# dcf77_clock.net
KiCad netlist of a schematic drawn in EAGLE
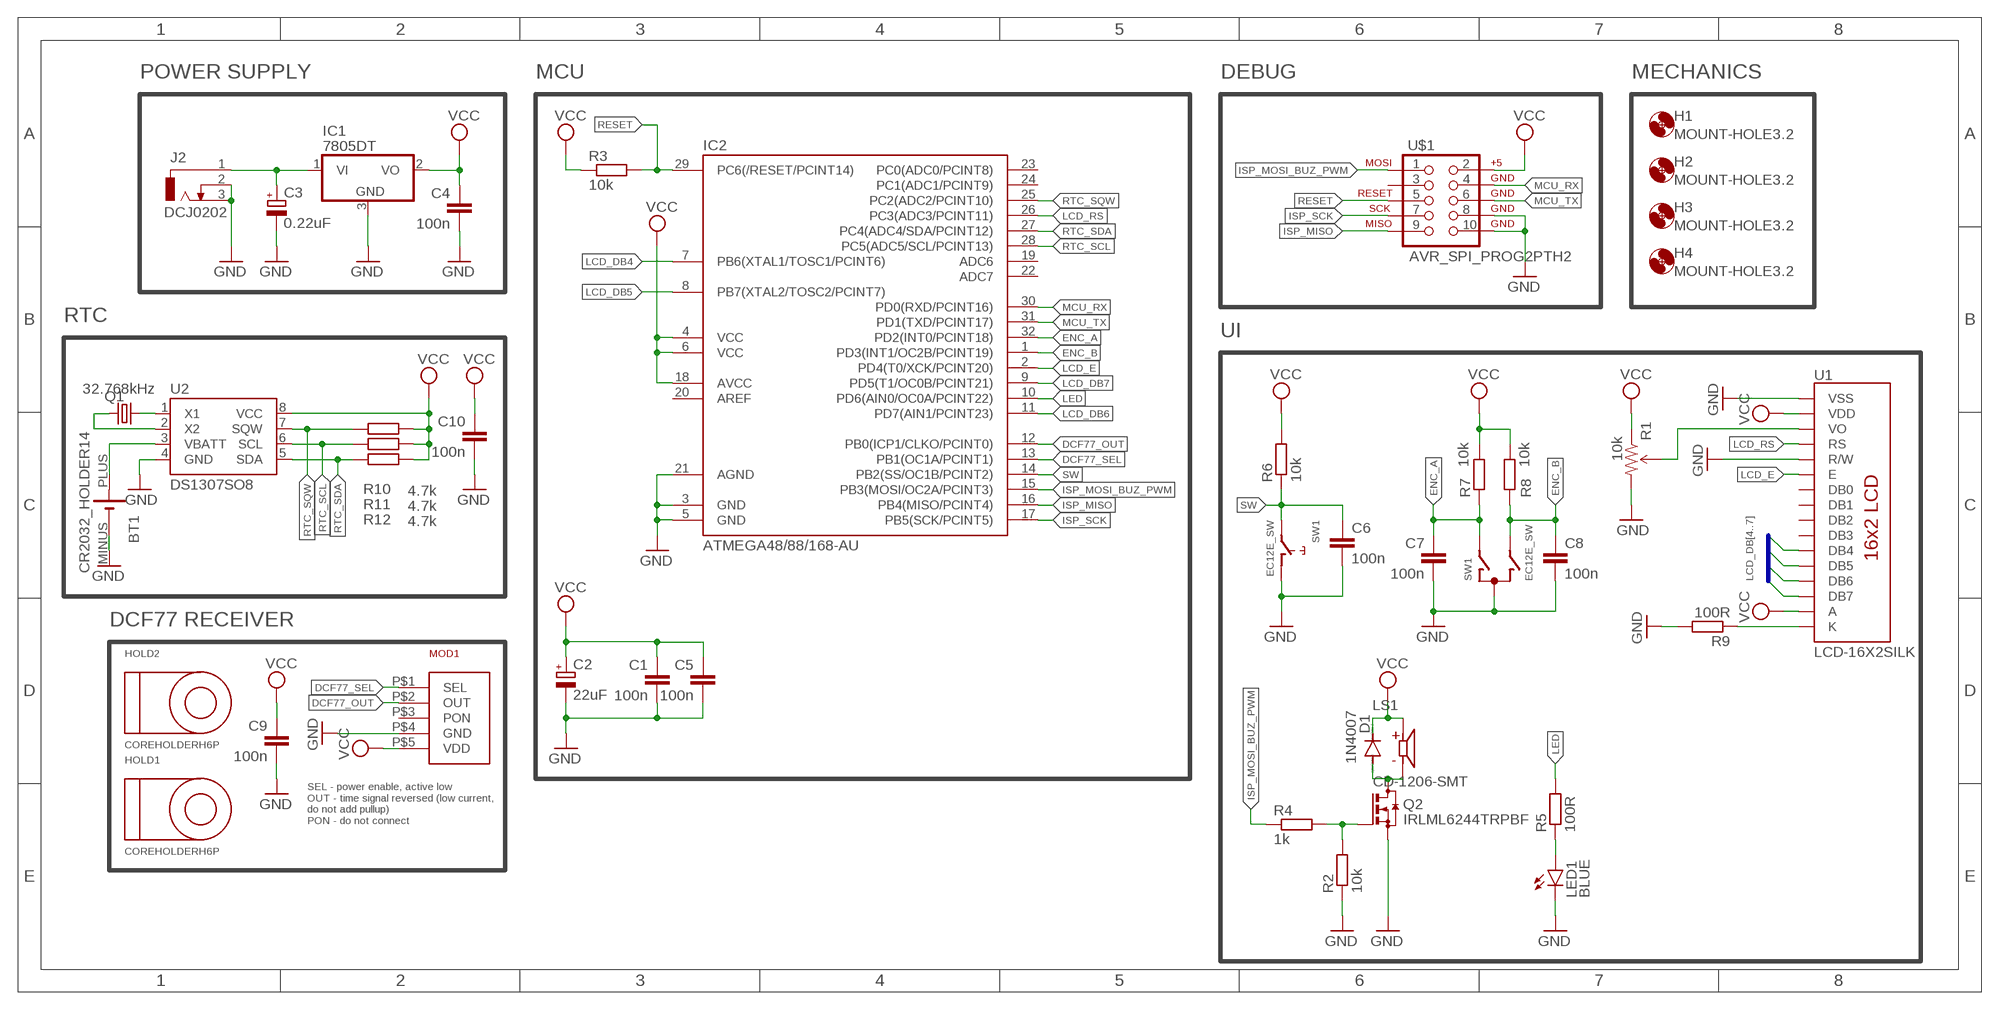
[diagram p0: schematic, sheet 1]

(export (version "E")
  (design (tool "Eeschema 10.0.6"))
  (components
    (comp (ref "BT1")
      (value "CR2032_HOLDER14")
      (footprint "eagle-import:CONNFLY-DS1092-14-B6P")
      (libsource (lib "eagle-import") (part "CR2032_HOLDER14"))
    )
    (comp (ref "C1")
      (value "100n")
      (footprint "eagle-import:C0805K")
      (libsource (lib "eagle-import") (part "C-EUC0805K"))
    )
    (comp (ref "C2")
      (value "22uF")
      (footprint "eagle-import:UD-4X5,8_NICHICON")
      (libsource (lib "eagle-import") (part "CPOL-EUUD-4X5,8"))
    )
    (comp (ref "C3")
      (value "0.22uF")
      (footprint "eagle-import:SMC_Z")
      (libsource (lib "eagle-import") (part "CPOL-EUSMCZ"))
    )
    (comp (ref "C4")
      (value "100n")
      (footprint "eagle-import:C0805K")
      (libsource (lib "eagle-import") (part "C-EUC0805K"))
    )
    (comp (ref "C5")
      (value "100n")
      (footprint "eagle-import:C0805K")
      (libsource (lib "eagle-import") (part "C-EUC0805K"))
    )
    (comp (ref "C6")
      (value "100n")
      (footprint "eagle-import:C0805K")
      (libsource (lib "eagle-import") (part "C-EUC0805K"))
    )
    (comp (ref "C7")
      (value "100n")
      (footprint "eagle-import:C0805K")
      (libsource (lib "eagle-import") (part "C-EUC0805K"))
    )
    (comp (ref "C8")
      (value "100n")
      (footprint "eagle-import:C0805K")
      (libsource (lib "eagle-import") (part "C-EUC0805K"))
    )
    (comp (ref "C9")
      (value "100n")
      (footprint "eagle-import:C0805K")
      (libsource (lib "eagle-import") (part "C-EUC0805K"))
    )
    (comp (ref "C10")
      (value "100n")
      (footprint "eagle-import:C0805K")
      (libsource (lib "eagle-import") (part "C-EUC0805K"))
    )
    (comp (ref "D1")
      (value "1N4007")
      (footprint "eagle-import:SOD123")
      (libsource (lib "eagle-import") (part "DIODE-SOD123"))
    )
    (comp (ref "H1")
      (value "MOUNT-HOLE3.2")
      (footprint "eagle-import:3,2")
      (libsource (lib "eagle-import") (part "MOUNT-HOLE3.2"))
    )
    (comp (ref "H2")
      (value "MOUNT-HOLE3.2")
      (footprint "eagle-import:3,2")
      (libsource (lib "eagle-import") (part "MOUNT-HOLE3.2"))
    )
    (comp (ref "H3")
      (value "MOUNT-HOLE3.2")
      (footprint "eagle-import:3,2")
      (libsource (lib "eagle-import") (part "MOUNT-HOLE3.2"))
    )
    (comp (ref "H4")
      (value "MOUNT-HOLE3.2")
      (footprint "eagle-import:3,2")
      (libsource (lib "eagle-import") (part "MOUNT-HOLE3.2"))
    )
    (comp (ref "HOLD1")
      (value "COREHOLDERH6P")
      (footprint "eagle-import:H6P")
      (libsource (lib "eagle-import") (part "COREHOLDERH6P"))
    )
    (comp (ref "HOLD2")
      (value "COREHOLDERH6P")
      (footprint "eagle-import:H6P")
      (libsource (lib "eagle-import") (part "COREHOLDERH6P"))
    )
    (comp (ref "IC1")
      (value "7805DT")
      (footprint "eagle-import:TO252")
      (libsource (lib "eagle-import") (part "78DT05"))
    )
    (comp (ref "IC2")
      (value "ATMEGA48/88/168-AU")
      (footprint "eagle-import:TQFP32-08")
      (libsource (lib "eagle-import") (part "ATMEGA48/88/168-AU"))
    )
    (comp (ref "J2")
      (value "DCJ0202")
      (footprint "eagle-import:DCJ0202")
      (libsource (lib "eagle-import") (part "DCJ0202"))
    )
    (comp (ref "LED1")
      (value "BLUE")
      (footprint "eagle-import:CHIP-LED0805")
      (libsource (lib "eagle-import") (part "LEDCHIP-LED0805"))
    )
    (comp (ref "LS1")
      (value "CD-1206-SMT")
      (footprint "eagle-import:CUI_CD-1206-SMT")
      (fields (field (name "MF") "CUI Inc.") (field (name "MP") "CD-1206-SMT-TR"))
      (libsource (lib "eagle-import") (part "CD-1206-SMT"))
    )
    (comp (ref "MOD1")
      (value "DCF77MODULE")
      (footprint "eagle-import:DCF77MOD")
      (libsource (lib "eagle-import") (part "DCF77MODULE"))
    )
    (comp (ref "Q1")
      (value "32.768kHz")
      (footprint "eagle-import:MM20SS")
      (libsource (lib "eagle-import") (part "CRYSTALMM20SS"))
    )
    (comp (ref "Q2")
      (value "IRLML6244TRPBF")
      (footprint "eagle-import:SOT23")
      (libsource (lib "eagle-import") (part "IRLML6244TRPBF"))
    )
    (comp (ref "R1")
      (value "10k")
      (footprint "eagle-import:TRIM_POT_PTH")
      (libsource (lib "eagle-import") (part "TRIMPOTPTH"))
    )
    (comp (ref "R2")
      (value "10k")
      (footprint "eagle-import:M0805")
      (libsource (lib "eagle-import") (part "R-EU_M0805"))
    )
    (comp (ref "R3")
      (value "10k")
      (footprint "eagle-import:M0805")
      (libsource (lib "eagle-import") (part "R-EU_M0805"))
    )
    (comp (ref "R4")
      (value "1k")
      (footprint "eagle-import:M0805")
      (libsource (lib "eagle-import") (part "R-EU_M0805"))
    )
    (comp (ref "R5")
      (value "100R")
      (footprint "eagle-import:M0805")
      (libsource (lib "eagle-import") (part "R-EU_M0805"))
    )
    (comp (ref "R6")
      (value "10k")
      (footprint "eagle-import:M0805")
      (libsource (lib "eagle-import") (part "R-EU_M0805"))
    )
    (comp (ref "R7")
      (value "10k")
      (footprint "eagle-import:M0805")
      (libsource (lib "eagle-import") (part "R-EU_M0805"))
    )
    (comp (ref "R8")
      (value "10k")
      (footprint "eagle-import:M0805")
      (libsource (lib "eagle-import") (part "R-EU_M0805"))
    )
    (comp (ref "R9")
      (value "100R")
      (footprint "eagle-import:M0805")
      (libsource (lib "eagle-import") (part "R-EU_M0805"))
    )
    (comp (ref "R10")
      (value "4.7k")
      (footprint "eagle-import:M0805")
      (libsource (lib "eagle-import") (part "R-EU_M0805"))
    )
    (comp (ref "R11")
      (value "4.7k")
      (footprint "eagle-import:M0805")
      (libsource (lib "eagle-import") (part "R-EU_M0805"))
    )
    (comp (ref "R12")
      (value "4.7k")
      (footprint "eagle-import:M0805")
      (libsource (lib "eagle-import") (part "R-EU_M0805"))
    )
    (comp (ref "SW1")
      (value "EC12E_SW")
      (footprint "eagle-import:ALPS_EC12E_SW")
      (fields (field (name "MPN") "EC12E2424407"))
      (libsource (lib "eagle-import") (part "EC12E_SW"))
    )
    (comp (ref "U$1")
      (value "AVR_SPI_PROG2PTH2")
      (footprint "eagle-import:2X5-SHROUDED")
      (libsource (lib "eagle-import") (part "AVR_SPI_PROG2PTH2"))
    )
    (comp (ref "U1")
      (value "LCD-16X2SILK")
      (footprint "eagle-import:LCD-16X2")
      (libsource (lib "eagle-import") (part "LCD-16X2SILK"))
    )
    (comp (ref "U2")
      (value "DS1307SO8")
      (footprint "eagle-import:SO08")
      (libsource (lib "eagle-import") (part "DS1307SO8"))
    )
  )
  (nets
    (net (code "2") (name "DCF77_OUT") (class "Default")
      (node (ref "IC2") (pin "12") (pinfunction "PB0(ICP1/CLKO/PCINT0)_12") (pintype "bidirectional"))
      (node (ref "MOD1") (pin "P$2") (pinfunction "OUT_P$2") (pintype "bidirectional"))
    )
    (net (code "3") (name "DCF77_SEL") (class "Default")
      (node (ref "IC2") (pin "13") (pinfunction "PB1(OC1A/PCINT1)_13") (pintype "bidirectional"))
      (node (ref "MOD1") (pin "P$1") (pinfunction "SEL_P$1") (pintype "bidirectional"))
    )
    (net (code "4") (name "ENC_A") (class "Default")
      (node (ref "C7") (pin "1") (pinfunction "1_1") (pintype "passive"))
      (node (ref "IC2") (pin "32") (pinfunction "PD2(INT0/PCINT18)_32") (pintype "bidirectional"))
      (node (ref "R7") (pin "1") (pinfunction "1_1") (pintype "passive"))
      (node (ref "SW1") (pin "A") (pinfunction "A_A") (pintype "passive"))
    )
    (net (code "5") (name "ENC_B") (class "Default")
      (node (ref "C8") (pin "1") (pinfunction "1_1") (pintype "passive"))
      (node (ref "IC2") (pin "1") (pinfunction "PD3(INT1/OC2B/PCINT19)_1") (pintype "bidirectional"))
      (node (ref "R8") (pin "1") (pinfunction "1_1") (pintype "passive"))
      (node (ref "SW1") (pin "B") (pinfunction "B_B") (pintype "passive"))
    )
    (net (code "6") (name "GND") (class "Default")
      (node (ref "BT1") (pin "MINUS") (pinfunction "MINUS_MINUS") (pintype "passive"))
      (node (ref "C1") (pin "2") (pinfunction "2_2") (pintype "passive"))
      (node (ref "C10") (pin "2") (pinfunction "2_2") (pintype "passive"))
      (node (ref "C2") (pin "-") (pinfunction "-_-") (pintype "passive"))
      (node (ref "C3") (pin "-") (pinfunction "-_-") (pintype "passive"))
      (node (ref "C4") (pin "2") (pinfunction "2_2") (pintype "passive"))
      (node (ref "C5") (pin "2") (pinfunction "2_2") (pintype "passive"))
      (node (ref "C6") (pin "2") (pinfunction "2_2") (pintype "passive"))
      (node (ref "C7") (pin "2") (pinfunction "2_2") (pintype "passive"))
      (node (ref "C8") (pin "2") (pinfunction "2_2") (pintype "passive"))
      (node (ref "C9") (pin "2") (pinfunction "2_2") (pintype "passive"))
      (node (ref "IC1") (pin "3") (pinfunction "GND_3") (pintype "passive"))
      (node (ref "IC2") (pin "21") (pinfunction "AGND_21") (pintype "power_in"))
      (node (ref "IC2") (pin "3") (pinfunction "GND_3") (pintype "power_in"))
      (node (ref "IC2") (pin "5") (pinfunction "GND_5") (pintype "power_in"))
      (node (ref "J2") (pin "2") (pinfunction "2_2") (pintype "passive"))
      (node (ref "J2") (pin "3") (pinfunction "3_3") (pintype "passive"))
      (node (ref "LED1") (pin "C") (pinfunction "C_C") (pintype "passive"))
      (node (ref "MOD1") (pin "P$4") (pinfunction "GND_P$4") (pintype "bidirectional"))
      (node (ref "Q2") (pin "2") (pinfunction "S_2") (pintype "passive"))
      (node (ref "R1") (pin "3") (pinfunction "CW_3") (pintype "passive"))
      (node (ref "R2") (pin "1") (pinfunction "1_1") (pintype "passive"))
      (node (ref "R9") (pin "2") (pinfunction "2_2") (pintype "passive"))
      (node (ref "SW1") (pin "C") (pinfunction "C_C") (pintype "passive"))
      (node (ref "SW1") (pin "D") (pinfunction "1_D") (pintype "passive"))
      (node (ref "U$1") (pin "10") (pinfunction "10_10") (pintype "passive"))
      (node (ref "U$1") (pin "8") (pinfunction "8_8") (pintype "passive"))
      (node (ref "U1") (pin "1") (pinfunction "VSS_1") (pintype "power_in"))
      (node (ref "U1") (pin "5") (pinfunction "R/W_5") (pintype "input"))
      (node (ref "U2") (pin "4") (pinfunction "GND_4") (pintype "bidirectional"))
    )
    (net (code "7") (name "ISP_MISO") (class "Default")
      (node (ref "IC2") (pin "16") (pinfunction "PB4(MISO/PCINT4)_16") (pintype "bidirectional"))
      (node (ref "U$1") (pin "9") (pinfunction "9_9") (pintype "passive"))
    )
    (net (code "8") (name "ISP_MOSI_BUZ_PWM") (class "Default")
      (node (ref "IC2") (pin "15") (pinfunction "PB3(MOSI/OC2A/PCINT3)_15") (pintype "bidirectional"))
      (node (ref "R4") (pin "1") (pinfunction "1_1") (pintype "passive"))
      (node (ref "U$1") (pin "1") (pinfunction "1_1") (pintype "passive"))
    )
    (net (code "9") (name "ISP_SCK") (class "Default")
      (node (ref "IC2") (pin "17") (pinfunction "PB5(SCK/PCINT5)_17") (pintype "bidirectional"))
      (node (ref "U$1") (pin "7") (pinfunction "7_7") (pintype "passive"))
    )
    (net (code "10") (name "LCD_DB4") (class "Default")
      (node (ref "IC2") (pin "7") (pinfunction "PB6(XTAL1/TOSC1/PCINT6)_7") (pintype "bidirectional"))
      (node (ref "U1") (pin "11") (pinfunction "DB4_11") (pintype "bidirectional"))
    )
    (net (code "11") (name "LCD_DB5") (class "Default")
      (node (ref "IC2") (pin "8") (pinfunction "PB7(XTAL2/TOSC2/PCINT7)_8") (pintype "bidirectional"))
      (node (ref "U1") (pin "12") (pinfunction "DB5_12") (pintype "bidirectional"))
    )
    (net (code "12") (name "LCD_DB6") (class "Default")
      (node (ref "IC2") (pin "11") (pinfunction "PD7(AIN1/PCINT23)_11") (pintype "bidirectional"))
      (node (ref "U1") (pin "13") (pinfunction "DB6_13") (pintype "bidirectional"))
    )
    (net (code "13") (name "LCD_DB7") (class "Default")
      (node (ref "IC2") (pin "9") (pinfunction "PD5(T1/OC0B/PCINT21)_9") (pintype "bidirectional"))
      (node (ref "U1") (pin "14") (pinfunction "DB7_14") (pintype "bidirectional"))
    )
    (net (code "14") (name "LCD_E") (class "Default")
      (node (ref "IC2") (pin "2") (pinfunction "PD4(T0/XCK/PCINT20)_2") (pintype "bidirectional"))
      (node (ref "U1") (pin "6") (pinfunction "E_6") (pintype "input"))
    )
    (net (code "15") (name "LCD_RS") (class "Default")
      (node (ref "IC2") (pin "26") (pinfunction "PC3(ADC3/PCINT11)_26") (pintype "bidirectional"))
      (node (ref "U1") (pin "4") (pinfunction "RS_4") (pintype "input"))
    )
    (net (code "16") (name "LED") (class "Default")
      (node (ref "IC2") (pin "10") (pinfunction "PD6(AIN0/OC0A/PCINT22)_10") (pintype "bidirectional"))
      (node (ref "R5") (pin "2") (pinfunction "2_2") (pintype "passive"))
    )
    (net (code "17") (name "MCU_RX") (class "Default")
      (node (ref "IC2") (pin "30") (pinfunction "PD0(RXD/PCINT16)_30") (pintype "bidirectional"))
      (node (ref "U$1") (pin "4") (pinfunction "4_4") (pintype "passive"))
    )
    (net (code "18") (name "MCU_TX") (class "Default")
      (node (ref "IC2") (pin "31") (pinfunction "PD1(TXD/PCINT17)_31") (pintype "bidirectional"))
      (node (ref "U$1") (pin "6") (pinfunction "6_6") (pintype "passive"))
    )
    (net (code "19") (name "Net-(IC1-VI)") (class "Default")
      (node (ref "C3") (pin "+") (pinfunction "+_+") (pintype "passive"))
      (node (ref "IC1") (pin "1") (pinfunction "VI_1") (pintype "input"))
      (node (ref "J2") (pin "1") (pinfunction "1_1") (pintype "passive"))
    )
    (net (code "20") (name "Net-(LED1-PadA)") (class "Default")
      (node (ref "LED1") (pin "A") (pinfunction "A_A") (pintype "passive"))
      (node (ref "R5") (pin "1") (pinfunction "1_1") (pintype "passive"))
    )
    (net (code "21") (name "Net-(Q1-2)") (class "Default")
      (node (ref "Q1") (pin "4") (pinfunction "2_4") (pintype "passive"))
      (node (ref "U2") (pin "2") (pinfunction "X2_2") (pintype "bidirectional"))
    )
    (net (code "22") (name "Net-(Q2-D)") (class "Default")
      (node (ref "D1") (pin "A") (pinfunction "A_A") (pintype "passive"))
      (node (ref "LS1") (pin "M") (pinfunction "M_M") (pintype "passive"))
      (node (ref "Q2") (pin "3") (pinfunction "D_3") (pintype "passive"))
    )
    (net (code "23") (name "Net-(Q2-G)") (class "Default")
      (node (ref "Q2") (pin "1") (pinfunction "G_1") (pintype "passive"))
      (node (ref "R2") (pin "2") (pinfunction "2_2") (pintype "passive"))
      (node (ref "R4") (pin "2") (pinfunction "2_2") (pintype "passive"))
    )
    (net (code "24") (name "Net-(R1-WIPER)") (class "Default")
      (node (ref "R1") (pin "2") (pinfunction "WIPER_2") (pintype "passive"))
      (node (ref "U1") (pin "3") (pinfunction "VO_3") (pintype "bidirectional"))
    )
    (net (code "25") (name "Net-(U1-K)") (class "Default")
      (node (ref "R9") (pin "1") (pinfunction "1_1") (pintype "passive"))
      (node (ref "U1") (pin "16") (pinfunction "K_16") (pintype "power_in"))
    )
    (net (code "26") (name "Net-(U2-VBATT)") (class "Default")
      (node (ref "BT1") (pin "PLUS") (pinfunction "PLUS_PLUS") (pintype "passive"))
      (node (ref "U2") (pin "3") (pinfunction "VBATT_3") (pintype "bidirectional"))
    )
    (net (code "27") (name "Net-(U2-X1)") (class "Default")
      (node (ref "Q1") (pin "1") (pinfunction "1_1") (pintype "passive"))
      (node (ref "U2") (pin "1") (pinfunction "X1_1") (pintype "bidirectional"))
    )
    (net (code "28") (name "RESET") (class "Default")
      (node (ref "IC2") (pin "29") (pinfunction "PC6(/RESET/PCINT14)_29") (pintype "bidirectional"))
      (node (ref "R3") (pin "2") (pinfunction "2_2") (pintype "passive"))
      (node (ref "U$1") (pin "5") (pinfunction "5_5") (pintype "passive"))
    )
    (net (code "29") (name "RTC_SCL") (class "Default")
      (node (ref "IC2") (pin "28") (pinfunction "PC5(ADC5/SCL/PCINT13)_28") (pintype "bidirectional"))
      (node (ref "R11") (pin "2") (pinfunction "2_2") (pintype "passive"))
      (node (ref "U2") (pin "6") (pinfunction "SCL_6") (pintype "bidirectional"))
    )
    (net (code "30") (name "RTC_SDA") (class "Default")
      (node (ref "IC2") (pin "27") (pinfunction "PC4(ADC4/SDA/PCINT12)_27") (pintype "bidirectional"))
      (node (ref "R12") (pin "2") (pinfunction "2_2") (pintype "passive"))
      (node (ref "U2") (pin "5") (pinfunction "SDA_5") (pintype "bidirectional"))
    )
    (net (code "31") (name "RTC_SQW") (class "Default")
      (node (ref "IC2") (pin "25") (pinfunction "PC2(ADC2/PCINT10)_25") (pintype "bidirectional"))
      (node (ref "R10") (pin "2") (pinfunction "2_2") (pintype "passive"))
      (node (ref "U2") (pin "7") (pinfunction "SQW_7") (pintype "bidirectional"))
    )
    (net (code "32") (name "SW") (class "Default")
      (node (ref "C6") (pin "1") (pinfunction "1_1") (pintype "passive"))
      (node (ref "IC2") (pin "14") (pinfunction "PB2(SS/OC1B/PCINT2)_14") (pintype "bidirectional"))
      (node (ref "R6") (pin "1") (pinfunction "1_1") (pintype "passive"))
      (node (ref "SW1") (pin "E") (pinfunction "2_E") (pintype "passive"))
    )
    (net (code "33") (name "VCC") (class "Default")
      (node (ref "C1") (pin "1") (pinfunction "1_1") (pintype "passive"))
      (node (ref "C10") (pin "1") (pinfunction "1_1") (pintype "passive"))
      (node (ref "C2") (pin "+") (pinfunction "+_+") (pintype "passive"))
      (node (ref "C4") (pin "1") (pinfunction "1_1") (pintype "passive"))
      (node (ref "C5") (pin "1") (pinfunction "1_1") (pintype "passive"))
      (node (ref "C9") (pin "1") (pinfunction "1_1") (pintype "passive"))
      (node (ref "D1") (pin "C") (pinfunction "C_C") (pintype "passive"))
      (node (ref "IC1") (pin "2") (pinfunction "VO_2") (pintype "passive"))
      (node (ref "IC2") (pin "18") (pinfunction "AVCC_18") (pintype "passive"))
      (node (ref "IC2") (pin "4") (pinfunction "VCC_4") (pintype "power_in"))
      (node (ref "IC2") (pin "6") (pinfunction "VCC_6") (pintype "power_in"))
      (node (ref "LS1") (pin "P") (pinfunction "P_P") (pintype "passive"))
      (node (ref "MOD1") (pin "P$5") (pinfunction "VDD_P$5") (pintype "bidirectional"))
      (node (ref "R1") (pin "1") (pinfunction "CCW_1") (pintype "passive"))
      (node (ref "R10") (pin "1") (pinfunction "1_1") (pintype "passive"))
      (node (ref "R11") (pin "1") (pinfunction "1_1") (pintype "passive"))
      (node (ref "R12") (pin "1") (pinfunction "1_1") (pintype "passive"))
      (node (ref "R3") (pin "1") (pinfunction "1_1") (pintype "passive"))
      (node (ref "R6") (pin "2") (pinfunction "2_2") (pintype "passive"))
      (node (ref "R7") (pin "2") (pinfunction "2_2") (pintype "passive"))
      (node (ref "R8") (pin "2") (pinfunction "2_2") (pintype "passive"))
      (node (ref "U$1") (pin "2") (pinfunction "2_2") (pintype "passive"))
      (node (ref "U1") (pin "15") (pinfunction "A_15") (pintype "power_in"))
      (node (ref "U1") (pin "2") (pinfunction "VDD_2") (pintype "power_in"))
      (node (ref "U2") (pin "8") (pinfunction "VCC_8") (pintype "bidirectional"))
    )
    (net (code "34") (name "unconnected-(IC2-ADC6-Pad19)") (class "Default")
      (node (ref "IC2") (pin "19") (pinfunction "ADC6_19") (pintype "passive"))
    )
    (net (code "35") (name "unconnected-(IC2-ADC7-Pad22)") (class "Default")
      (node (ref "IC2") (pin "22") (pinfunction "ADC7_22") (pintype "passive"))
    )
    (net (code "36") (name "unconnected-(IC2-AREF-Pad20)") (class "Default")
      (node (ref "IC2") (pin "20") (pinfunction "AREF_20") (pintype "passive"))
    )
    (net (code "37") (name "unconnected-(IC2-PC0(ADC0{slash}PCINT8)-Pad23)") (class "Default")
      (node (ref "IC2") (pin "23") (pinfunction "PC0(ADC0/PCINT8)_23") (pintype "bidirectional"))
    )
    (net (code "38") (name "unconnected-(IC2-PC1(ADC1{slash}PCINT9)-Pad24)") (class "Default")
      (node (ref "IC2") (pin "24") (pinfunction "PC1(ADC1/PCINT9)_24") (pintype "bidirectional"))
    )
    (net (code "39") (name "unconnected-(MOD1-PON-PadP$3)") (class "Default")
      (node (ref "MOD1") (pin "P$3") (pinfunction "PON_P$3") (pintype "bidirectional"))
    )
    (net (code "40") (name "unconnected-(U$1-Pad3)") (class "Default")
      (node (ref "U$1") (pin "3") (pinfunction "3_3") (pintype "passive"))
    )
    (net (code "41") (name "unconnected-(U1-DB0-Pad7)") (class "Default")
      (node (ref "U1") (pin "7") (pinfunction "DB0_7") (pintype "bidirectional"))
    )
    (net (code "42") (name "unconnected-(U1-DB1-Pad8)") (class "Default")
      (node (ref "U1") (pin "8") (pinfunction "DB1_8") (pintype "bidirectional"))
    )
    (net (code "43") (name "unconnected-(U1-DB2-Pad9)") (class "Default")
      (node (ref "U1") (pin "9") (pinfunction "DB2_9") (pintype "bidirectional"))
    )
    (net (code "44") (name "unconnected-(U1-DB3-Pad10)") (class "Default")
      (node (ref "U1") (pin "10") (pinfunction "DB3_10") (pintype "bidirectional"))
    )
  )
)
